# BQ34110.net
KiCad netlist of a schematic drawn in Altium Designer
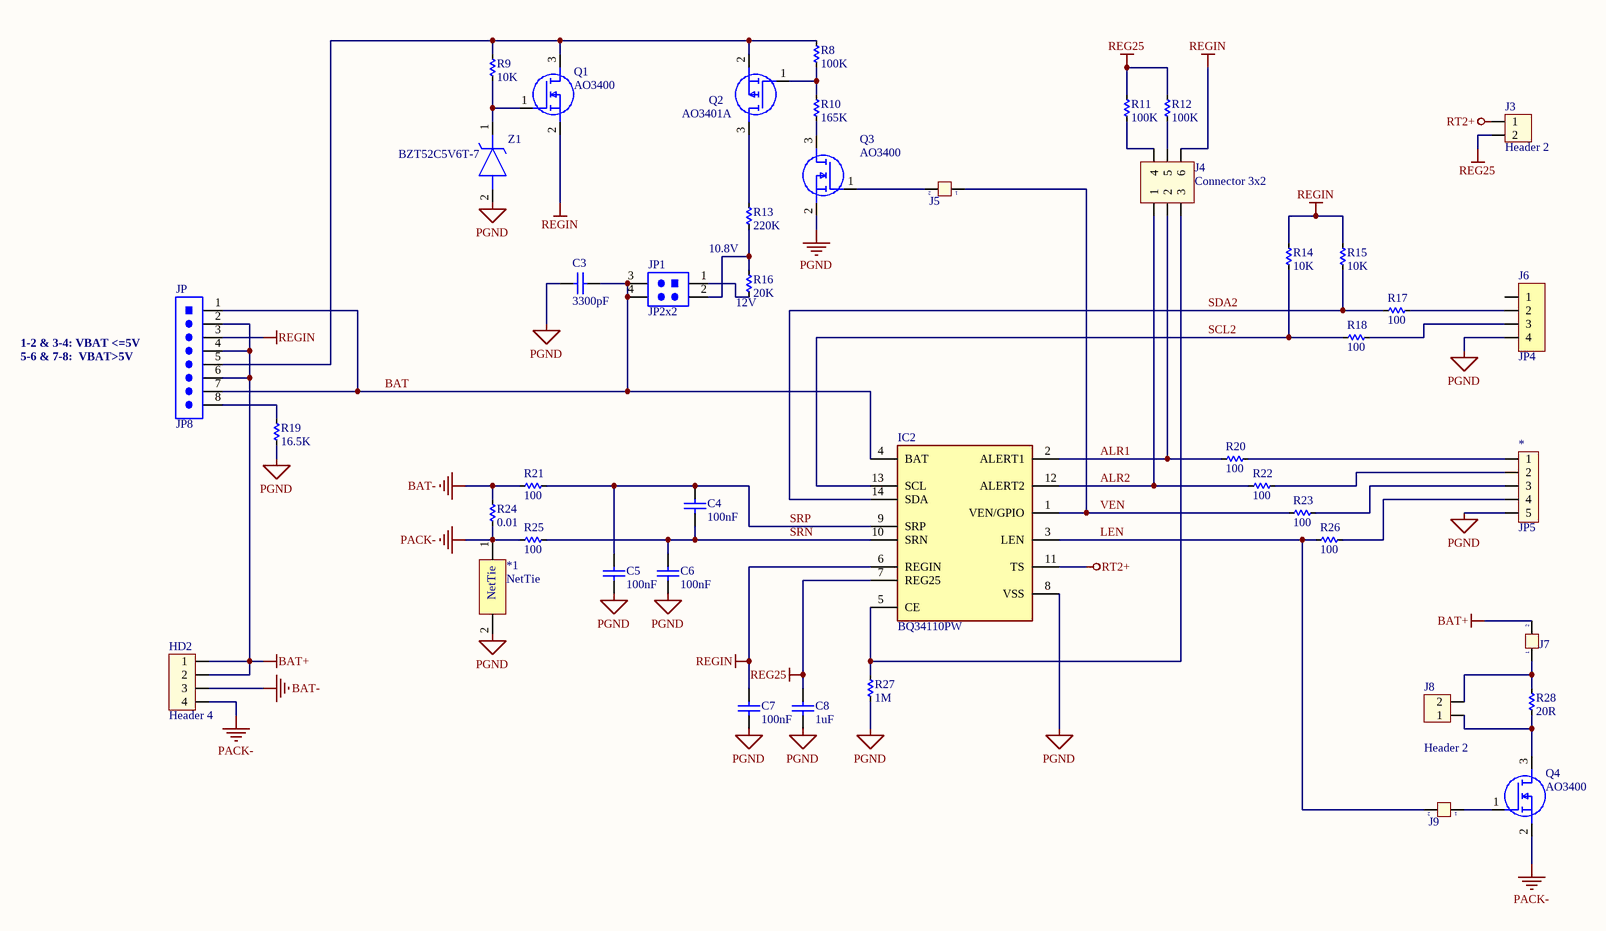
[diagram p0: BQ34110.SchDoc]

(export (version "E")
  (design (tool "Eeschema 10.0.6"))
  (components
    (comp (ref "*") (value "JP5") (footprint "JP5") (libsource (lib "syhaunguyen") (part "JP5")))
    (comp (ref "*1") (value "NetTie") (footprint "NetTie") (libsource (lib "PhanBach") (part "NetTie")))
    (comp (ref "C3")
      (value "3300pF")
      (footprint "0805 CAP")
      (fields (field (name "PUBLISHER") "Altium Limited"))
      (libsource (lib "ThinhNguyenLib") (part "CAP CERAMIC"))
    )
    (comp (ref "C4")
      (value "100nF")
      (footprint "0805 CAP")
      (fields (field (name "PUBLISHER") "Altium Limited"))
      (libsource (lib "ThinhNguyenLib") (part "CAP CERAMIC"))
    )
    (comp (ref "C5")
      (value "100nF")
      (footprint "0805 CAP")
      (fields (field (name "PUBLISHER") "Altium Limited"))
      (libsource (lib "ThinhNguyenLib") (part "CAP CERAMIC"))
    )
    (comp (ref "C6")
      (value "100nF")
      (footprint "0805 CAP")
      (fields (field (name "PUBLISHER") "Altium Limited"))
      (libsource (lib "ThinhNguyenLib") (part "CAP CERAMIC"))
    )
    (comp (ref "C7")
      (value "100nF")
      (footprint "0805 CAP")
      (fields (field (name "PUBLISHER") "Altium Limited"))
      (libsource (lib "ThinhNguyenLib") (part "CAP CERAMIC"))
    )
    (comp (ref "C8")
      (value "1uF")
      (footprint "0805 CAP")
      (fields (field (name "PUBLISHER") "Altium Limited"))
      (libsource (lib "ThinhNguyenLib") (part "CAP CERAMIC"))
    )
    (comp (ref "HD2")
      (value "Header 4")
      (footprint "HED4")
      (description "Header 4 (Green)")
      (libsource (lib "syhaunguyen") (part "Hed4"))
    )
    (comp (ref "IC2")
      (value "BQ34110PW")
      (footprint "SamacSys:SOP65P640X120-14N")
      (description "Integrated Circuit")
      (fields (field (name "MOUSER PART NUMBER") "595-BQ34110PW"))
      (libsource (lib "SamacSys") (part "BQ34110PW"))
    )
    (comp (ref "J3")
      (value "Header 2")
      (footprint "HED2B")
      (description "Header 2 (Green)")
      (libsource (lib "") (part "Hed2_1"))
    )
    (comp (ref "J4")
      (value "Connector 3x2")
      (footprint "JP3x2")
      (libsource (lib "syhaunguyen") (part "JP3x2"))
    )
    (comp (ref "J5") (value "Jumper 2") (footprint "JP2") (libsource (lib "library") (part "JP 2")))
    (comp (ref "J6")
      (value "JP4")
      (footprint "JP4-C1T")
      (description "WR-PHD 2.54 mm Angled Socket Header")
      (fields
        (field (name "MANUFACTURER") "Würth Elektronik eiSos GmbH")
        (field (name "PARTNO") "613004143121")
        (field (name "CREATED BY") "Karrer Zheng")
      )
      (libsource (lib "LIBRARY1") (part "JP4"))
    )
    (comp (ref "J7") (value "Jumper 2") (footprint "JP2") (libsource (lib "") (part "JP 2_1")))
    (comp (ref "J8")
      (value "Header 2")
      (footprint "HED2B")
      (description "Header 2 (Green)")
      (libsource (lib "syhaunguyen") (part "Hed2"))
    )
    (comp (ref "J9") (value "Jumper 2") (footprint "JP2") (libsource (lib "library") (part "JP 2")))
    (comp (ref "JP") (value "JP8") (footprint "JP8") (libsource (lib "PhanBach") (part "JP8")))
    (comp (ref "JP1") (value "JP2x2") (footprint "JP2X2") (libsource (lib "PhanBach") (part "JP2x2")))
    (comp (ref "Q1")
      (value "AO3400")
      (footprint "SamacSys:SOT95P280X125-3N")
      (description "MOSFET (N-Channel)")
      (libsource (lib "*") (part "AO3400"))
    )
    (comp (ref "Q2")
      (value "AO3401A")
      (footprint "SamacSys:SOT95P280X125-3N")
      (description "MOSFET (P-Channel)")
      (libsource (lib "*") (part "AO3401A"))
    )
    (comp (ref "Q3")
      (value "AO3400")
      (footprint "SamacSys:SOT95P280X125-3N")
      (description "MOSFET (N-Channel)")
      (libsource (lib "*") (part "AO3400"))
    )
    (comp (ref "Q4")
      (value "AO3400")
      (footprint "SamacSys:SOT95P280X125-3N")
      (description "MOSFET (N-Channel)")
      (libsource (lib "*") (part "AO3400"))
    )
    (comp (ref "R8")
      (value "100K")
      (footprint "RES-SMD-0805")
      (description "Resistor")
      (fields
        (field (name "MANUFACTURER") "Generic Components")
        (field (name "PUBLISHER") "Altium Hobart Technology Centre")
      )
      (libsource (lib "LIBRARY1") (part "Res-SMD"))
    )
    (comp (ref "R9")
      (value "10K")
      (footprint "RES-SMD-0805")
      (description "Resistor")
      (fields
        (field (name "MANUFACTURER") "Generic Components")
        (field (name "PUBLISHER") "Altium Hobart Technology Centre")
      )
      (libsource (lib "LIBRARY1") (part "Res-SMD"))
    )
    (comp (ref "R10")
      (value "165K")
      (footprint "RES-SMD-0805")
      (description "Resistor")
      (fields
        (field (name "MANUFACTURER") "Generic Components")
        (field (name "PUBLISHER") "Altium Hobart Technology Centre")
      )
      (libsource (lib "LIBRARY1") (part "Res-SMD"))
    )
    (comp (ref "R11")
      (value "100K")
      (footprint "RES-SMD-0805")
      (description "Resistor")
      (fields
        (field (name "MANUFACTURER") "Generic Components")
        (field (name "PUBLISHER") "Altium Hobart Technology Centre")
      )
      (libsource (lib "LIBRARY1") (part "Res-SMD"))
    )
    (comp (ref "R12")
      (value "100K")
      (footprint "RES-SMD-0805")
      (description "Resistor")
      (fields
        (field (name "MANUFACTURER") "Generic Components")
        (field (name "PUBLISHER") "Altium Hobart Technology Centre")
      )
      (libsource (lib "LIBRARY1") (part "Res-SMD"))
    )
    (comp (ref "R13")
      (value "220K")
      (footprint "RES-SMD-0805")
      (description "Resistor")
      (fields
        (field (name "MANUFACTURER") "Generic Components")
        (field (name "PUBLISHER") "Altium Hobart Technology Centre")
      )
      (libsource (lib "LIBRARY1") (part "Res-SMD"))
    )
    (comp (ref "R14")
      (value "10K")
      (footprint "RES-SMD-0805")
      (description "Resistor")
      (fields
        (field (name "MANUFACTURER") "Generic Components")
        (field (name "PUBLISHER") "Altium Hobart Technology Centre")
      )
      (libsource (lib "LIBRARY1") (part "Res-SMD"))
    )
    (comp (ref "R15")
      (value "10K")
      (footprint "RES-SMD-0805")
      (description "Resistor")
      (fields
        (field (name "MANUFACTURER") "Generic Components")
        (field (name "PUBLISHER") "Altium Hobart Technology Centre")
      )
      (libsource (lib "LIBRARY1") (part "Res-SMD"))
    )
    (comp (ref "R16")
      (value "20K")
      (footprint "RES-SMD-0805")
      (description "Resistor")
      (fields
        (field (name "MANUFACTURER") "Generic Components")
        (field (name "PUBLISHER") "Altium Hobart Technology Centre")
      )
      (libsource (lib "LIBRARY1") (part "Res-SMD"))
    )
    (comp (ref "R17")
      (value "100")
      (footprint "RES-SMD-0805")
      (description "Resistor")
      (fields
        (field (name "MANUFACTURER") "Generic Components")
        (field (name "PUBLISHER") "Altium Hobart Technology Centre")
      )
      (libsource (lib "LIBRARY1") (part "Res-SMD"))
    )
    (comp (ref "R18")
      (value "100")
      (footprint "RES-SMD-0805")
      (description "Resistor")
      (fields
        (field (name "MANUFACTURER") "Generic Components")
        (field (name "PUBLISHER") "Altium Hobart Technology Centre")
      )
      (libsource (lib "LIBRARY1") (part "Res-SMD"))
    )
    (comp (ref "R19")
      (value "16.5K")
      (footprint "RES-SMD-0805")
      (description "Resistor")
      (fields
        (field (name "MANUFACTURER") "Generic Components")
        (field (name "PUBLISHER") "Altium Hobart Technology Centre")
      )
      (libsource (lib "LIBRARY1") (part "Res-SMD"))
    )
    (comp (ref "R20")
      (value "100")
      (footprint "RES-SMD-0805")
      (description "Resistor")
      (fields
        (field (name "MANUFACTURER") "Generic Components")
        (field (name "PUBLISHER") "Altium Hobart Technology Centre")
      )
      (libsource (lib "LIBRARY1") (part "Res-SMD"))
    )
    (comp (ref "R21")
      (value "100")
      (footprint "RES-SMD-0805")
      (description "Resistor")
      (fields
        (field (name "MANUFACTURER") "Generic Components")
        (field (name "PUBLISHER") "Altium Hobart Technology Centre")
      )
      (libsource (lib "LIBRARY1") (part "Res-SMD"))
    )
    (comp (ref "R22")
      (value "100")
      (footprint "RES-SMD-0805")
      (description "Resistor")
      (fields
        (field (name "MANUFACTURER") "Generic Components")
        (field (name "PUBLISHER") "Altium Hobart Technology Centre")
      )
      (libsource (lib "LIBRARY1") (part "Res-SMD"))
    )
    (comp (ref "R23")
      (value "100")
      (footprint "RES-SMD-0805")
      (description "Resistor")
      (fields
        (field (name "MANUFACTURER") "Generic Components")
        (field (name "PUBLISHER") "Altium Hobart Technology Centre")
      )
      (libsource (lib "LIBRARY1") (part "Res-SMD"))
    )
    (comp (ref "R24")
      (value "0.01")
      (footprint "RES-SMD-0805")
      (description "Resistor")
      (fields
        (field (name "MANUFACTURER") "Generic Components")
        (field (name "PUBLISHER") "Altium Hobart Technology Centre")
      )
      (libsource (lib "LIBRARY1") (part "Res-SMD"))
    )
    (comp (ref "R25")
      (value "100")
      (footprint "RES-SMD-0805")
      (description "Resistor")
      (fields
        (field (name "MANUFACTURER") "Generic Components")
        (field (name "PUBLISHER") "Altium Hobart Technology Centre")
      )
      (libsource (lib "LIBRARY1") (part "Res-SMD"))
    )
    (comp (ref "R26")
      (value "100")
      (footprint "RES-SMD-0805")
      (description "Resistor")
      (fields
        (field (name "MANUFACTURER") "Generic Components")
        (field (name "PUBLISHER") "Altium Hobart Technology Centre")
      )
      (libsource (lib "LIBRARY1") (part "Res-SMD"))
    )
    (comp (ref "R27")
      (value "1M")
      (footprint "RES-SMD-0805")
      (description "Resistor")
      (fields
        (field (name "MANUFACTURER") "Generic Components")
        (field (name "PUBLISHER") "Altium Hobart Technology Centre")
      )
      (libsource (lib "LIBRARY1") (part "Res-SMD"))
    )
    (comp (ref "R28")
      (value "20R")
      (footprint "RES-SMD-2512")
      (description "Resistor")
      (fields
        (field (name "MANUFACTURER") "Generic Components")
        (field (name "PUBLISHER") "Altium Hobart Technology Centre")
      )
      (libsource (lib "LIBRARY1") (part "Res-SMD"))
    )
    (comp (ref "Z1")
      (value "BZT52C5V6T-7")
      (footprint "SamacSys:SODFL1608X65N")
      (description "Zener Diode")
      (fields (field (name "MOUSER PART NUMBER") "621-BZT52C5V6T-7"))
      (libsource (lib "*") (part "BZT52C5V6T-7"))
    )
  )
  (nets
    (net (code "1") (name "/ALR1") (class "Default")
      (node (ref "IC2") (pin "2") (pinfunction "ALERT1_2") (pintype "passive"))
      (node (ref "J4") (pin "5") (pinfunction "2_5") (pintype "passive"))
      (node (ref "R20") (pin "1") (pinfunction "1_1") (pintype "passive"))
    )
    (net (code "2") (name "/ALR2") (class "Default")
      (node (ref "IC2") (pin "12") (pinfunction "ALERT2_12") (pintype "passive"))
      (node (ref "J4") (pin "1") (pinfunction "1_1") (pintype "passive"))
      (node (ref "R22") (pin "1") (pinfunction "1_1") (pintype "passive"))
    )
    (net (code "3") (name "/BAT") (class "Default")
      (node (ref "C3") (pin "1") (pinfunction "1_1") (pintype "passive"))
      (node (ref "IC2") (pin "4") (pinfunction "BAT_4") (pintype "passive"))
      (node (ref "JP") (pin "1") (pinfunction "1_1") (pintype "passive"))
      (node (ref "JP") (pin "7") (pinfunction "7_7") (pintype "passive"))
      (node (ref "JP1") (pin "3") (pinfunction "3_3") (pintype "passive"))
      (node (ref "JP1") (pin "4") (pinfunction "4_4") (pintype "passive"))
    )
    (net (code "4") (name "/LEN") (class "Default")
      (node (ref "IC2") (pin "3") (pinfunction "LEN_3") (pintype "passive"))
      (node (ref "J9") (pin "2") (pinfunction "2_2") (pintype "passive"))
      (node (ref "R26") (pin "1") (pinfunction "1_1") (pintype "passive"))
    )
    (net (code "5") (name "/SCL2") (class "Default")
      (node (ref "IC2") (pin "13") (pinfunction "SCL_13") (pintype "passive"))
      (node (ref "R14") (pin "1") (pinfunction "1_1") (pintype "passive"))
      (node (ref "R18") (pin "1") (pinfunction "1_1") (pintype "passive"))
    )
    (net (code "6") (name "/SDA2") (class "Default")
      (node (ref "IC2") (pin "14") (pinfunction "SDA_14") (pintype "passive"))
      (node (ref "R15") (pin "1") (pinfunction "1_1") (pintype "passive"))
      (node (ref "R17") (pin "1") (pinfunction "1_1") (pintype "passive"))
    )
    (net (code "7") (name "/SRN") (class "Default")
      (node (ref "C4") (pin "2") (pinfunction "2_2") (pintype "passive"))
      (node (ref "C6") (pin "1") (pinfunction "1_1") (pintype "passive"))
      (node (ref "IC2") (pin "10") (pinfunction "SRN_10") (pintype "passive"))
      (node (ref "R25") (pin "2") (pinfunction "2_2") (pintype "passive"))
    )
    (net (code "8") (name "/SRP") (class "Default")
      (node (ref "C4") (pin "1") (pinfunction "1_1") (pintype "passive"))
      (node (ref "C5") (pin "1") (pinfunction "1_1") (pintype "passive"))
      (node (ref "IC2") (pin "9") (pinfunction "SRP_9") (pintype "passive"))
      (node (ref "R21") (pin "2") (pinfunction "2_2") (pintype "passive"))
    )
    (net (code "9") (name "/VEN") (class "Default")
      (node (ref "IC2") (pin "1") (pinfunction "VEN/GPIO_1") (pintype "passive"))
      (node (ref "J5") (pin "1") (pinfunction "1_1") (pintype "passive"))
      (node (ref "R23") (pin "1") (pinfunction "1_1") (pintype "passive"))
    )
    (net (code "10") (name "BAT+") (class "Default")
      (node (ref "HD2") (pin "1") (pinfunction "1_1") (pintype "passive"))
      (node (ref "HD2") (pin "2") (pinfunction "2_2") (pintype "passive"))
      (node (ref "J7") (pin "2") (pinfunction "2_2") (pintype "passive"))
      (node (ref "JP") (pin "2") (pinfunction "2_2") (pintype "passive"))
      (node (ref "JP") (pin "4") (pinfunction "4_4") (pintype "passive"))
      (node (ref "JP") (pin "6") (pinfunction "6_6") (pintype "passive"))
    )
    (net (code "11") (name "BAT-") (class "Default")
      (node (ref "HD2") (pin "3") (pinfunction "3_3") (pintype "passive"))
      (node (ref "R21") (pin "1") (pinfunction "1_1") (pintype "passive"))
      (node (ref "R24") (pin "1") (pinfunction "1_1") (pintype "passive"))
    )
    (net (code "12") (name "Net-(*-Pad1)") (class "Default")
      (node (ref "*") (pin "1") (pinfunction "1_1") (pintype "passive"))
      (node (ref "R20") (pin "2") (pinfunction "2_2") (pintype "passive"))
    )
    (net (code "13") (name "Net-(*-Pad2)") (class "Default")
      (node (ref "*") (pin "2") (pinfunction "2_2") (pintype "passive"))
      (node (ref "R22") (pin "2") (pinfunction "2_2") (pintype "passive"))
    )
    (net (code "14") (name "Net-(*-Pad3)") (class "Default")
      (node (ref "*") (pin "3") (pinfunction "3_3") (pintype "passive"))
      (node (ref "R23") (pin "2") (pinfunction "2_2") (pintype "passive"))
    )
    (net (code "15") (name "Net-(*-Pad4)") (class "Default")
      (node (ref "*") (pin "4") (pinfunction "4_4") (pintype "passive"))
      (node (ref "R26") (pin "2") (pinfunction "2_2") (pintype "passive"))
    )
    (net (code "16") (name "Net-(IC2-CE)") (class "Default")
      (node (ref "IC2") (pin "5") (pinfunction "CE_5") (pintype "passive"))
      (node (ref "J4") (pin "6") (pinfunction "3_6") (pintype "passive"))
      (node (ref "R27") (pin "1") (pinfunction "1_1") (pintype "passive"))
    )
    (net (code "17") (name "Net-(J4-5)") (class "Default")
      (node (ref "J4") (pin "2") (pinfunction "5_2") (pintype "passive"))
      (node (ref "R12") (pin "1") (pinfunction "1_1") (pintype "passive"))
    )
    (net (code "18") (name "Net-(J4-Pad4)") (class "Default")
      (node (ref "J4") (pin "4") (pinfunction "4_4") (pintype "passive"))
      (node (ref "R11") (pin "1") (pinfunction "1_1") (pintype "passive"))
    )
    (net (code "19") (name "Net-(J6-Pad2)") (class "Default")
      (node (ref "J6") (pin "2") (pinfunction "2_2") (pintype "passive"))
      (node (ref "R17") (pin "2") (pinfunction "2_2") (pintype "passive"))
    )
    (net (code "20") (name "Net-(J6-Pad3)") (class "Default")
      (node (ref "J6") (pin "3") (pinfunction "3_3") (pintype "passive"))
      (node (ref "R18") (pin "2") (pinfunction "2_2") (pintype "passive"))
    )
    (net (code "21") (name "Net-(J7-Pad1)") (class "Default")
      (node (ref "J7") (pin "1") (pinfunction "1_1") (pintype "passive"))
      (node (ref "J8") (pin "2") (pinfunction "2_2") (pintype "passive"))
      (node (ref "R28") (pin "2") (pinfunction "2_2") (pintype "passive"))
    )
    (net (code "22") (name "Net-(JP-Pad8)") (class "Default")
      (node (ref "JP") (pin "8") (pinfunction "8_8") (pintype "passive"))
      (node (ref "R19") (pin "2") (pinfunction "2_2") (pintype "passive"))
    )
    (net (code "23") (name "Net-(JP1-Pad1)") (class "Default")
      (node (ref "JP1") (pin "1") (pinfunction "1_1") (pintype "passive"))
      (node (ref "R16") (pin "1") (pinfunction "1_1") (pintype "passive"))
    )
    (net (code "24") (name "Net-(JP1-Pad2)") (class "Default")
      (node (ref "JP1") (pin "2") (pinfunction "2_2") (pintype "passive"))
      (node (ref "R13") (pin "1") (pinfunction "1_1") (pintype "passive"))
      (node (ref "R16") (pin "2") (pinfunction "2_2") (pintype "passive"))
    )
    (net (code "25") (name "Net-(Q1-D)") (class "Default")
      (node (ref "JP") (pin "5") (pinfunction "5_5") (pintype "passive"))
      (node (ref "Q1") (pin "3") (pinfunction "D_3") (pintype "passive"))
      (node (ref "Q2") (pin "2") (pinfunction "S_2") (pintype "passive"))
      (node (ref "R8") (pin "2") (pinfunction "2_2") (pintype "passive"))
      (node (ref "R9") (pin "2") (pinfunction "2_2") (pintype "passive"))
    )
    (net (code "26") (name "Net-(Q1-G)") (class "Default")
      (node (ref "Q1") (pin "1") (pinfunction "G_1") (pintype "passive"))
      (node (ref "R9") (pin "1") (pinfunction "1_1") (pintype "passive"))
      (node (ref "Z1") (pin "1") (pinfunction "K_1") (pintype "passive"))
    )
    (net (code "27") (name "Net-(Q2-D)") (class "Default")
      (node (ref "Q2") (pin "3") (pinfunction "D_3") (pintype "passive"))
      (node (ref "R13") (pin "2") (pinfunction "2_2") (pintype "passive"))
    )
    (net (code "28") (name "Net-(Q2-G)") (class "Default")
      (node (ref "Q2") (pin "1") (pinfunction "G_1") (pintype "passive"))
      (node (ref "R10") (pin "2") (pinfunction "2_2") (pintype "passive"))
      (node (ref "R8") (pin "1") (pinfunction "1_1") (pintype "passive"))
    )
    (net (code "29") (name "Net-(Q3-D)") (class "Default")
      (node (ref "Q3") (pin "3") (pinfunction "D_3") (pintype "passive"))
      (node (ref "R10") (pin "1") (pinfunction "1_1") (pintype "passive"))
    )
    (net (code "30") (name "Net-(Q3-G)") (class "Default")
      (node (ref "J5") (pin "2") (pinfunction "2_2") (pintype "passive"))
      (node (ref "Q3") (pin "1") (pinfunction "G_1") (pintype "passive"))
    )
    (net (code "31") (name "Net-(Q4-D)") (class "Default")
      (node (ref "J8") (pin "1") (pinfunction "1_1") (pintype "passive"))
      (node (ref "Q4") (pin "3") (pinfunction "D_3") (pintype "passive"))
      (node (ref "R28") (pin "1") (pinfunction "1_1") (pintype "passive"))
    )
    (net (code "32") (name "Net-(Q4-G)") (class "Default")
      (node (ref "J9") (pin "1") (pinfunction "1_1") (pintype "passive"))
      (node (ref "Q4") (pin "1") (pinfunction "G_1") (pintype "passive"))
    )
    (net (code "33") (name "PACK-") (class "Default")
      (node (ref "*1") (pin "1") (pinfunction "43_1") (pintype "passive"))
      (node (ref "HD2") (pin "4") (pinfunction "4_4") (pintype "passive"))
      (node (ref "Q4") (pin "2") (pinfunction "S_2") (pintype "passive"))
      (node (ref "R24") (pin "2") (pinfunction "2_2") (pintype "passive"))
      (node (ref "R25") (pin "1") (pinfunction "1_1") (pintype "passive"))
    )
    (net (code "34") (name "PGND") (class "Default")
      (node (ref "*") (pin "5") (pinfunction "5_5") (pintype "passive"))
      (node (ref "*1") (pin "2") (pinfunction "2_2") (pintype "passive"))
      (node (ref "C3") (pin "2") (pinfunction "2_2") (pintype "passive"))
      (node (ref "C5") (pin "2") (pinfunction "2_2") (pintype "passive"))
      (node (ref "C6") (pin "2") (pinfunction "2_2") (pintype "passive"))
      (node (ref "C7") (pin "2") (pinfunction "2_2") (pintype "passive"))
      (node (ref "C8") (pin "2") (pinfunction "2_2") (pintype "passive"))
      (node (ref "IC2") (pin "8") (pinfunction "VSS_8") (pintype "passive"))
      (node (ref "J6") (pin "4") (pinfunction "4_4") (pintype "passive"))
      (node (ref "Q3") (pin "2") (pinfunction "S_2") (pintype "passive"))
      (node (ref "R19") (pin "1") (pinfunction "1_1") (pintype "passive"))
      (node (ref "R27") (pin "2") (pinfunction "2_2") (pintype "passive"))
      (node (ref "Z1") (pin "2") (pinfunction "A_2") (pintype "passive"))
    )
    (net (code "35") (name "REG25") (class "Default")
      (node (ref "C8") (pin "1") (pinfunction "1_1") (pintype "passive"))
      (node (ref "IC2") (pin "7") (pinfunction "REG25_7") (pintype "passive"))
      (node (ref "J3") (pin "2") (pinfunction "2_2") (pintype "passive"))
      (node (ref "R11") (pin "2") (pinfunction "2_2") (pintype "passive"))
      (node (ref "R12") (pin "2") (pinfunction "2_2") (pintype "passive"))
    )
    (net (code "36") (name "REGIN") (class "Default")
      (node (ref "C7") (pin "1") (pinfunction "1_1") (pintype "passive"))
      (node (ref "IC2") (pin "6") (pinfunction "REGIN_6") (pintype "passive"))
      (node (ref "J4") (pin "3") (pinfunction "6_3") (pintype "passive"))
      (node (ref "JP") (pin "3") (pinfunction "3_3") (pintype "passive"))
      (node (ref "Q1") (pin "2") (pinfunction "S_2") (pintype "passive"))
      (node (ref "R14") (pin "2") (pinfunction "2_2") (pintype "passive"))
      (node (ref "R15") (pin "2") (pinfunction "2_2") (pintype "passive"))
    )
    (net (code "37") (name "RT2+") (class "Default")
      (node (ref "IC2") (pin "11") (pinfunction "TS_11") (pintype "passive"))
      (node (ref "J3") (pin "1") (pinfunction "1_1") (pintype "passive"))
    )
    (net (code "38") (name "unconnected-(J6-Pad1)") (class "Default")
      (node (ref "J6") (pin "1") (pinfunction "1_1") (pintype "passive"))
    )
  )
)
